# CSM37F58_V6_1.net
KiCad netlist of a schematic drawn in Altium Designer
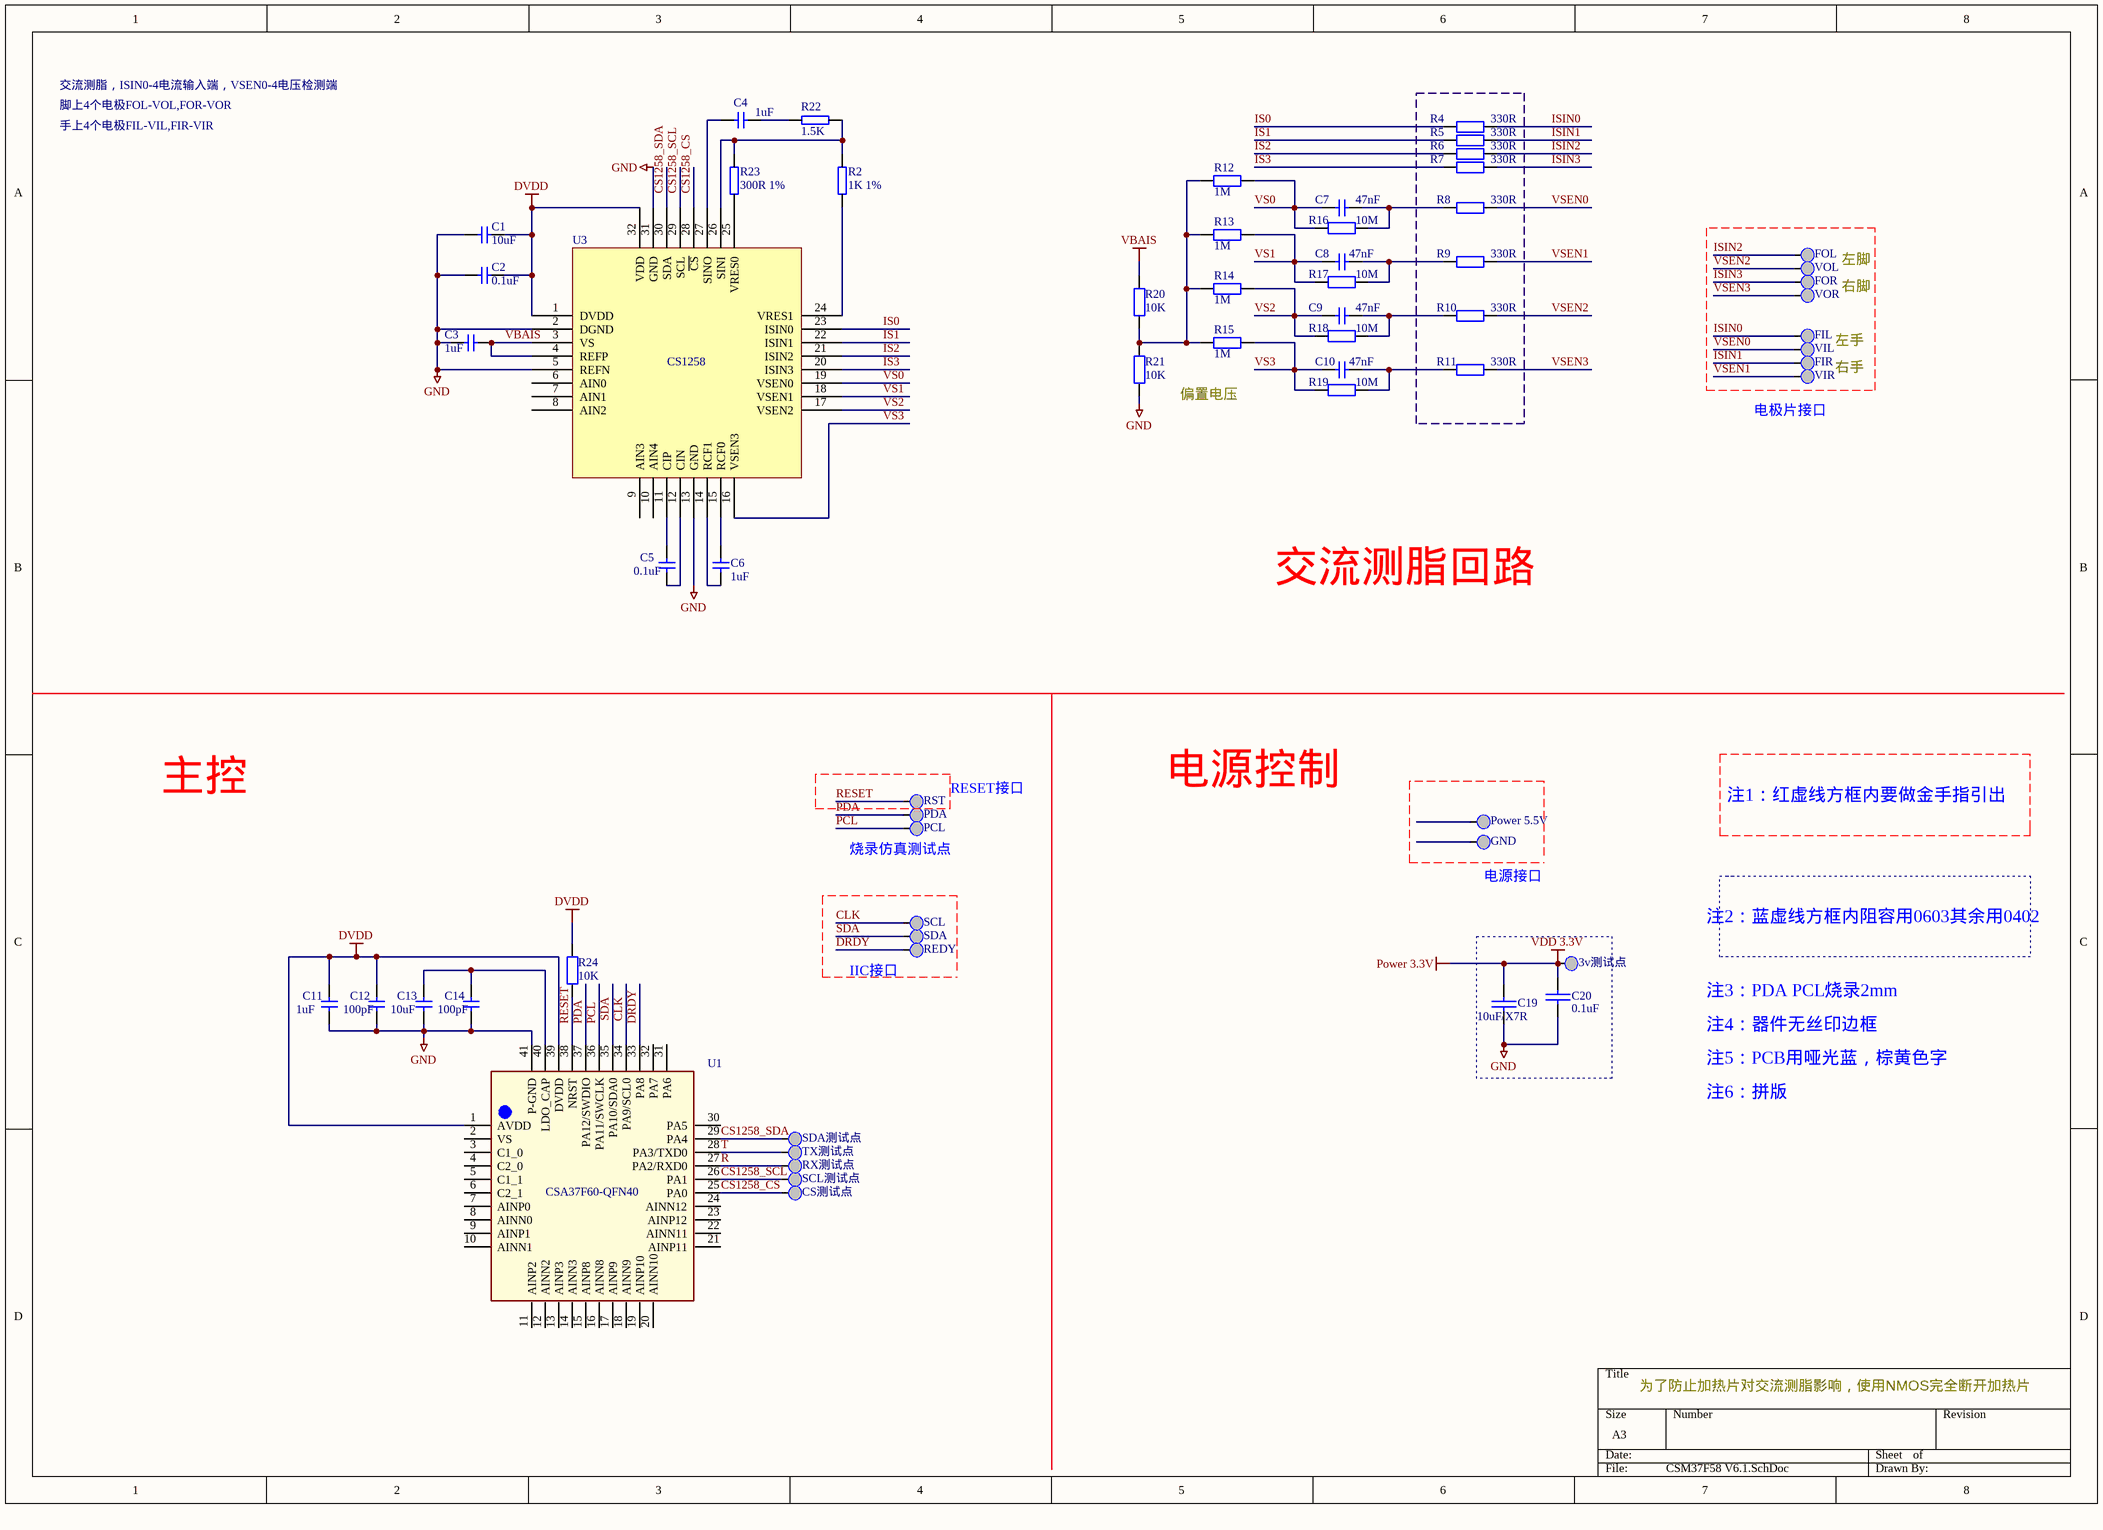
[diagram p0: CSM37F58 V6.1.SchDoc]

(export (version "E")
  (design (tool "Eeschema 10.0.6"))
  (components
    (comp (ref "3v测试点") (value "~") (footprint "TEST-SMD") (libsource (lib "*") (part "TESTPOINT")))
    (comp (ref "C1") (value "10uF") (footprint "C0603E") (libsource (lib "") (part "CAP_1")))
    (comp (ref "C2") (value "0.1uF") (footprint "C0603E") (libsource (lib "") (part "CAP_1")))
    (comp (ref "C3") (value "1uF") (footprint "C0603E") (libsource (lib "") (part "CAP_1")))
    (comp (ref "C4") (value "1uF") (footprint "C0603E") (libsource (lib "") (part "CAP_1")))
    (comp (ref "C5") (value "0.1uF") (footprint "C0603E") (libsource (lib "") (part "CAP_1")))
    (comp (ref "C6") (value "1uF") (footprint "C0603E") (libsource (lib "") (part "CAP_1")))
    (comp (ref "C7") (value "47nF") (footprint "C0603E") (libsource (lib "") (part "CAP_1")))
    (comp (ref "C8") (value "47nF") (footprint "C0603E") (libsource (lib "") (part "CAP_1")))
    (comp (ref "C9") (value "47nF") (footprint "C0603E") (libsource (lib "") (part "CAP_1")))
    (comp (ref "C10") (value "47nF") (footprint "C0603E") (libsource (lib "") (part "CAP_1")))
    (comp (ref "C11") (value "1uF") (footprint "C0603E") (libsource (lib "") (part "CAP_1")))
    (comp (ref "C12") (value "100pF") (footprint "C0603E") (libsource (lib "") (part "CAP_1")))
    (comp (ref "C13") (value "10uF") (footprint "C0603E") (libsource (lib "") (part "CAP_1")))
    (comp (ref "C14") (value "100pF") (footprint "C0603E") (libsource (lib "") (part "CAP_1")))
    (comp (ref "C19")
      (value "10uF/X7R")
      (footprint "C0603")
      (description "Capacitor")
      (libsource (lib "*") (part "CAP"))
    )
    (comp (ref "C20")
      (value "0.1uF")
      (footprint "C0603")
      (description "Capacitor")
      (libsource (lib "*") (part "CAP"))
    )
    (comp (ref "CS测试点") (value "~") (footprint "TEST-SMD") (libsource (lib "*") (part "TESTPOINT")))
    (comp (ref "FIL") (value "TESTPOINT") (footprint "TEST-SMD") (libsource (lib "*") (part "TESTPOINT")))
    (comp (ref "FIR") (value "TESTPOINT") (footprint "TEST-SMD") (libsource (lib "*") (part "TESTPOINT")))
    (comp (ref "FOL") (value "TESTPOINT") (footprint "TEST-SMD") (libsource (lib "*") (part "TESTPOINT")))
    (comp (ref "FOR") (value "TESTPOINT") (footprint "TEST-SMD") (libsource (lib "*") (part "TESTPOINT")))
    (comp (ref "GND") (value "~") (footprint "TEST-SMD") (libsource (lib "*") (part "TESTPOINT")))
    (comp (ref "PCL") (value "~") (footprint "TEST-SMD") (libsource (lib "*") (part "TESTPOINT")))
    (comp (ref "PDA") (value "~") (footprint "TEST-SMD") (libsource (lib "*") (part "TESTPOINT")))
    (comp (ref "Power 5.5V") (value "~") (footprint "TEST-SMD") (libsource (lib "*") (part "TESTPOINT")))
    (comp (ref "R2") (value "1K 1%") (footprint "R0603E") (libsource (lib "*") (part "RES")))
    (comp (ref "R4")
      (value "330R")
      (footprint "R0603E")
      (description "Resistor")
      (fields (field (name "Comment") "Res2") (field (name "PUBLISHER") "Altium Limited"))
      (libsource (lib "Miscellaneous Devices") (part "Res2"))
    )
    (comp (ref "R5")
      (value "330R")
      (footprint "R0603E")
      (description "Resistor")
      (fields (field (name "Comment") "Res2") (field (name "PUBLISHER") "Altium Limited"))
      (libsource (lib "Miscellaneous Devices") (part "Res2"))
    )
    (comp (ref "R6")
      (value "330R")
      (footprint "R0603E")
      (description "Resistor")
      (fields (field (name "Comment") "Res2") (field (name "PUBLISHER") "Altium Limited"))
      (libsource (lib "Miscellaneous Devices") (part "Res2"))
    )
    (comp (ref "R7")
      (value "330R")
      (footprint "R0603E")
      (description "Resistor")
      (fields (field (name "Comment") "Res2") (field (name "PUBLISHER") "Altium Limited"))
      (libsource (lib "Miscellaneous Devices") (part "Res2"))
    )
    (comp (ref "R8")
      (value "330R")
      (footprint "R0603E")
      (description "Resistor")
      (fields (field (name "Comment") "Res2") (field (name "PUBLISHER") "Altium Limited"))
      (libsource (lib "Miscellaneous Devices") (part "Res2"))
    )
    (comp (ref "R9")
      (value "330R")
      (footprint "R0603E")
      (description "Resistor")
      (fields (field (name "Comment") "Res2") (field (name "PUBLISHER") "Altium Limited"))
      (libsource (lib "Miscellaneous Devices") (part "Res2"))
    )
    (comp (ref "R10")
      (value "330R")
      (footprint "R0603E")
      (description "Resistor")
      (fields (field (name "Comment") "Res2") (field (name "PUBLISHER") "Altium Limited"))
      (libsource (lib "Miscellaneous Devices") (part "Res2"))
    )
    (comp (ref "R11")
      (value "330R")
      (footprint "R0603E")
      (description "Resistor")
      (fields (field (name "Comment") "Res2") (field (name "PUBLISHER") "Altium Limited"))
      (libsource (lib "") (part "Res2_1"))
    )
    (comp (ref "R12")
      (value "1M")
      (footprint "R0603E")
      (description "Resistor")
      (fields (field (name "Comment") "Res2") (field (name "PUBLISHER") "Altium Limited"))
      (libsource (lib "") (part "Res2_1"))
    )
    (comp (ref "R13")
      (value "1M")
      (footprint "R0603E")
      (description "Resistor")
      (fields (field (name "Comment") "Res2") (field (name "PUBLISHER") "Altium Limited"))
      (libsource (lib "") (part "Res2_1"))
    )
    (comp (ref "R14")
      (value "1M")
      (footprint "R0603E")
      (description "Resistor")
      (fields (field (name "Comment") "Res2") (field (name "PUBLISHER") "Altium Limited"))
      (libsource (lib "") (part "Res2_1"))
    )
    (comp (ref "R15")
      (value "1M")
      (footprint "R0603E")
      (description "Resistor")
      (fields (field (name "Comment") "Res2") (field (name "PUBLISHER") "Altium Limited"))
      (libsource (lib "") (part "Res2_1"))
    )
    (comp (ref "R16")
      (value "10M")
      (footprint "R0603E")
      (description "Resistor")
      (fields (field (name "Comment") "Res2") (field (name "PUBLISHER") "Altium Limited"))
      (libsource (lib "") (part "Res2_1"))
    )
    (comp (ref "R17")
      (value "10M")
      (footprint "R0603E")
      (description "Resistor")
      (fields (field (name "Comment") "Res2") (field (name "PUBLISHER") "Altium Limited"))
      (libsource (lib "") (part "Res2_1"))
    )
    (comp (ref "R18")
      (value "10M")
      (footprint "R0603E")
      (description "Resistor")
      (fields (field (name "Comment") "Res2") (field (name "PUBLISHER") "Altium Limited"))
      (libsource (lib "") (part "Res2_1"))
    )
    (comp (ref "R19")
      (value "10M")
      (footprint "R0603E")
      (description "Resistor")
      (fields (field (name "Comment") "Res2") (field (name "PUBLISHER") "Altium Limited"))
      (libsource (lib "") (part "Res2_1"))
    )
    (comp (ref "R20")
      (value "10K")
      (footprint "R0603E")
      (description "Resistor")
      (fields (field (name "Comment") "Res2") (field (name "PUBLISHER") "Altium Limited"))
      (libsource (lib "") (part "Res2_3"))
    )
    (comp (ref "R21")
      (value "10K")
      (footprint "R0603E")
      (description "Resistor")
      (fields (field (name "Comment") "Res2") (field (name "PUBLISHER") "Altium Limited"))
      (libsource (lib "") (part "Res2_2"))
    )
    (comp (ref "R22") (value "1.5K") (footprint "R0603E") (libsource (lib "*") (part "RES")))
    (comp (ref "R23") (value "300R 1%") (footprint "R0603E") (libsource (lib "*") (part "RES")))
    (comp (ref "R24")
      (value "10K")
      (footprint "R0603E")
      (description "Resistor")
      (fields (field (name "Comment") "Res2") (field (name "PUBLISHER") "Altium Limited"))
      (libsource (lib "") (part "Res2_2"))
    )
    (comp (ref "REDY") (value "~") (footprint "TEST-SMD") (libsource (lib "*") (part "TESTPOINT")))
    (comp (ref "RST") (value "~") (footprint "TEST-SMD") (libsource (lib "*") (part "TESTPOINT")))
    (comp (ref "RX测试点") (value "~") (footprint "TEST-SMD") (libsource (lib "*") (part "TESTPOINT")))
    (comp (ref "SCL") (value "~") (footprint "TEST-SMD") (libsource (lib "*") (part "TESTPOINT")))
    (comp (ref "SCL测试点") (value "~") (footprint "TEST-SMD") (libsource (lib "*") (part "TESTPOINT")))
    (comp (ref "SDA") (value "~") (footprint "TEST-SMD") (libsource (lib "*") (part "TESTPOINT")))
    (comp (ref "SDA测试点") (value "~") (footprint "TEST-SMD") (libsource (lib "*") (part "TESTPOINT")))
    (comp (ref "TX测试点") (value "~") (footprint "TEST-SMD") (libsource (lib "*") (part "TESTPOINT")))
    (comp (ref "U1")
      (value "CSA37F60-QFN40")
      (footprint "QFN40-04")
      (libsource (lib "Chipsea MCU") (part "CSA37F60-QFN40"))
    )
    (comp (ref "U3") (value "CS1258") (footprint "LQFP32") (libsource (lib "*") (part "CS1258")))
    (comp (ref "VIL") (value "TESTPOINT") (footprint "TEST-SMD") (libsource (lib "*") (part "TESTPOINT")))
    (comp (ref "VIR") (value "TESTPOINT") (footprint "TEST-SMD") (libsource (lib "*") (part "TESTPOINT")))
    (comp (ref "VOL") (value "TESTPOINT") (footprint "TEST-SMD") (libsource (lib "*") (part "TESTPOINT")))
    (comp (ref "VOR") (value "TESTPOINT") (footprint "TEST-SMD") (libsource (lib "*") (part "TESTPOINT")))
  )
  (nets
    (net (code "1") (name "/CLK") (class "Default")
      (node (ref "SCL") (pin "1") (pinfunction "1_1") (pintype "passive"))
      (node (ref "U1") (pin "34") (pinfunction "PA9/SCL0_34") (pintype "passive"))
    )
    (net (code "2") (name "/CS1258_CS") (class "Default")
      (node (ref "CS测试点") (pin "1") (pinfunction "1_1") (pintype "passive"))
      (node (ref "U1") (pin "25") (pinfunction "PA0_25") (pintype "passive"))
      (node (ref "U3") (pin "28") (pinfunction "~{CS}_28") (pintype "passive"))
    )
    (net (code "3") (name "/CS1258_SCL") (class "Default")
      (node (ref "SCL测试点") (pin "1") (pinfunction "1_1") (pintype "passive"))
      (node (ref "U1") (pin "26") (pinfunction "PA1_26") (pintype "passive"))
      (node (ref "U3") (pin "29") (pinfunction "SCL_29") (pintype "passive"))
    )
    (net (code "4") (name "/CS1258_SDA") (class "Default")
      (node (ref "SDA测试点") (pin "1") (pinfunction "1_1") (pintype "passive"))
      (node (ref "U1") (pin "29") (pinfunction "PA4_29") (pintype "passive"))
      (node (ref "U3") (pin "30") (pinfunction "SDA_30") (pintype "passive"))
    )
    (net (code "5") (name "/DRDY") (class "Default")
      (node (ref "REDY") (pin "1") (pinfunction "1_1") (pintype "passive"))
      (node (ref "U1") (pin "33") (pinfunction "PA8_33") (pintype "passive"))
    )
    (net (code "6") (name "/IS0") (class "Default")
      (node (ref "R4") (pin "1") (pinfunction "1_1") (pintype "passive"))
      (node (ref "U3") (pin "23") (pinfunction "ISIN0_23") (pintype "passive"))
    )
    (net (code "7") (name "/IS1") (class "Default")
      (node (ref "R5") (pin "1") (pinfunction "1_1") (pintype "passive"))
      (node (ref "U3") (pin "22") (pinfunction "ISIN1_22") (pintype "passive"))
    )
    (net (code "8") (name "/IS2") (class "Default")
      (node (ref "R6") (pin "1") (pinfunction "1_1") (pintype "passive"))
      (node (ref "U3") (pin "21") (pinfunction "ISIN2_21") (pintype "passive"))
    )
    (net (code "9") (name "/IS3") (class "Default")
      (node (ref "R7") (pin "1") (pinfunction "1_1") (pintype "passive"))
      (node (ref "U3") (pin "20") (pinfunction "ISIN3_20") (pintype "passive"))
    )
    (net (code "10") (name "/ISIN0") (class "Default")
      (node (ref "FIL") (pin "1") (pinfunction "1_1") (pintype "passive"))
      (node (ref "R4") (pin "2") (pinfunction "2_2") (pintype "passive"))
    )
    (net (code "11") (name "/ISIN1") (class "Default")
      (node (ref "FIR") (pin "1") (pinfunction "1_1") (pintype "passive"))
      (node (ref "R5") (pin "2") (pinfunction "2_2") (pintype "passive"))
    )
    (net (code "12") (name "/ISIN2") (class "Default")
      (node (ref "FOL") (pin "1") (pinfunction "1_1") (pintype "passive"))
      (node (ref "R6") (pin "2") (pinfunction "2_2") (pintype "passive"))
    )
    (net (code "13") (name "/ISIN3") (class "Default")
      (node (ref "FOR") (pin "1") (pinfunction "1_1") (pintype "passive"))
      (node (ref "R7") (pin "2") (pinfunction "2_2") (pintype "passive"))
    )
    (net (code "14") (name "/PCL") (class "Default")
      (node (ref "PCL") (pin "1") (pinfunction "1_1") (pintype "passive"))
      (node (ref "U1") (pin "36") (pinfunction "PA11/SWCLK_36") (pintype "passive"))
    )
    (net (code "15") (name "/PDA") (class "Default")
      (node (ref "PDA") (pin "1") (pinfunction "1_1") (pintype "passive"))
      (node (ref "U1") (pin "37") (pinfunction "PA12/SWDIO_37") (pintype "passive"))
    )
    (net (code "16") (name "/R") (class "Default")
      (node (ref "RX测试点") (pin "1") (pinfunction "1_1") (pintype "passive"))
      (node (ref "U1") (pin "27") (pinfunction "PA2/RXD0_27") (pintype "passive"))
    )
    (net (code "17") (name "/RESET") (class "Default")
      (node (ref "R24") (pin "1") (pinfunction "1_1") (pintype "passive"))
      (node (ref "RST") (pin "1") (pinfunction "1_1") (pintype "passive"))
      (node (ref "U1") (pin "38") (pinfunction "NRST_38") (pintype "passive"))
    )
    (net (code "18") (name "/SDA") (class "Default")
      (node (ref "SDA") (pin "1") (pinfunction "1_1") (pintype "passive"))
      (node (ref "U1") (pin "35") (pinfunction "PA10/SDA0_35") (pintype "passive"))
    )
    (net (code "19") (name "/T") (class "Default")
      (node (ref "TX测试点") (pin "1") (pinfunction "1_1") (pintype "passive"))
      (node (ref "U1") (pin "28") (pinfunction "PA3/TXD0_28") (pintype "passive"))
    )
    (net (code "20") (name "/VS0") (class "Default")
      (node (ref "C7") (pin "1") (pintype "passive"))
      (node (ref "R12") (pin "1") (pinfunction "1_1") (pintype "passive"))
      (node (ref "R16") (pin "2") (pinfunction "2_2") (pintype "passive"))
      (node (ref "U3") (pin "19") (pinfunction "VSEN0_19") (pintype "passive"))
    )
    (net (code "21") (name "/VS1") (class "Default")
      (node (ref "C8") (pin "1") (pintype "passive"))
      (node (ref "R13") (pin "1") (pinfunction "1_1") (pintype "passive"))
      (node (ref "R17") (pin "2") (pinfunction "2_2") (pintype "passive"))
      (node (ref "U3") (pin "18") (pinfunction "VSEN1_18") (pintype "passive"))
    )
    (net (code "22") (name "/VS2") (class "Default")
      (node (ref "C9") (pin "1") (pintype "passive"))
      (node (ref "R14") (pin "1") (pinfunction "1_1") (pintype "passive"))
      (node (ref "R18") (pin "2") (pinfunction "2_2") (pintype "passive"))
      (node (ref "U3") (pin "17") (pinfunction "VSEN2_17") (pintype "passive"))
    )
    (net (code "23") (name "/VS3") (class "Default")
      (node (ref "C10") (pin "1") (pintype "passive"))
      (node (ref "R15") (pin "1") (pinfunction "1_1") (pintype "passive"))
      (node (ref "R19") (pin "2") (pinfunction "2_2") (pintype "passive"))
      (node (ref "U3") (pin "16") (pinfunction "VSEN3_16") (pintype "passive"))
    )
    (net (code "24") (name "/VSEN0") (class "Default")
      (node (ref "R8") (pin "2") (pinfunction "2_2") (pintype "passive"))
      (node (ref "VIL") (pin "1") (pinfunction "1_1") (pintype "passive"))
    )
    (net (code "25") (name "/VSEN1") (class "Default")
      (node (ref "R9") (pin "2") (pinfunction "2_2") (pintype "passive"))
      (node (ref "VIR") (pin "1") (pinfunction "1_1") (pintype "passive"))
    )
    (net (code "26") (name "/VSEN2") (class "Default")
      (node (ref "R10") (pin "2") (pinfunction "2_2") (pintype "passive"))
      (node (ref "VOL") (pin "1") (pinfunction "1_1") (pintype "passive"))
    )
    (net (code "27") (name "/VSEN3") (class "Default")
      (node (ref "R11") (pin "1") (pinfunction "1_1") (pintype "passive"))
      (node (ref "VOR") (pin "1") (pinfunction "1_1") (pintype "passive"))
    )
    (net (code "28") (name "DVDD") (class "Default")
      (node (ref "C1") (pin "2") (pintype "passive"))
      (node (ref "C11") (pin "1") (pintype "passive"))
      (node (ref "C12") (pin "1") (pintype "passive"))
      (node (ref "C2") (pin "1") (pintype "passive"))
      (node (ref "R24") (pin "2") (pinfunction "2_2") (pintype "passive"))
      (node (ref "U1") (pin "1") (pinfunction "AVDD_1") (pintype "passive"))
      (node (ref "U1") (pin "39") (pinfunction "DVDD_39") (pintype "passive"))
      (node (ref "U3") (pin "1") (pinfunction "DVDD_1") (pintype "passive"))
      (node (ref "U3") (pin "32") (pinfunction "VDD_32") (pintype "passive"))
    )
    (net (code "29") (name "GND") (class "Default")
      (node (ref "C1") (pin "1") (pintype "passive"))
      (node (ref "C11") (pin "2") (pintype "passive"))
      (node (ref "C12") (pin "2") (pintype "passive"))
      (node (ref "C13") (pin "2") (pintype "passive"))
      (node (ref "C14") (pin "2") (pintype "passive"))
      (node (ref "C19") (pin "2") (pinfunction "2_2") (pintype "passive"))
      (node (ref "C2") (pin "2") (pintype "passive"))
      (node (ref "C20") (pin "2") (pinfunction "2_2") (pintype "passive"))
      (node (ref "C3") (pin "2") (pintype "passive"))
      (node (ref "R21") (pin "1") (pinfunction "1_1") (pintype "passive"))
      (node (ref "U1") (pin "41") (pinfunction "P-GND_41") (pintype "passive"))
      (node (ref "U3") (pin "13") (pinfunction "GND_13") (pintype "passive"))
      (node (ref "U3") (pin "2") (pinfunction "DGND_2") (pintype "passive"))
      (node (ref "U3") (pin "31") (pinfunction "GND_31") (pintype "passive"))
      (node (ref "U3") (pin "5") (pinfunction "REFN_5") (pintype "passive"))
    )
    (net (code "30") (name "Net-(C4-Pad1)") (class "Default")
      (node (ref "C4") (pin "1") (pintype "passive"))
      (node (ref "R22") (pin "2") (pintype "passive"))
    )
    (net (code "31") (name "Net-(C7-Pad2)") (class "Default")
      (node (ref "C7") (pin "2") (pintype "passive"))
      (node (ref "R16") (pin "1") (pinfunction "1_1") (pintype "passive"))
      (node (ref "R8") (pin "1") (pinfunction "1_1") (pintype "passive"))
    )
    (net (code "32") (name "Net-(C8-Pad2)") (class "Default")
      (node (ref "C8") (pin "2") (pintype "passive"))
      (node (ref "R17") (pin "1") (pinfunction "1_1") (pintype "passive"))
      (node (ref "R9") (pin "1") (pinfunction "1_1") (pintype "passive"))
    )
    (net (code "33") (name "Net-(C9-Pad2)") (class "Default")
      (node (ref "C9") (pin "2") (pintype "passive"))
      (node (ref "R10") (pin "1") (pinfunction "1_1") (pintype "passive"))
      (node (ref "R18") (pin "1") (pinfunction "1_1") (pintype "passive"))
    )
    (net (code "34") (name "Net-(C10-Pad2)") (class "Default")
      (node (ref "C10") (pin "2") (pintype "passive"))
      (node (ref "R11") (pin "2") (pinfunction "2_2") (pintype "passive"))
      (node (ref "R19") (pin "1") (pinfunction "1_1") (pintype "passive"))
    )
    (net (code "35") (name "Net-(R12-Pad2)") (class "Default")
      (node (ref "R12") (pin "2") (pinfunction "2_2") (pintype "passive"))
      (node (ref "R13") (pin "2") (pinfunction "2_2") (pintype "passive"))
      (node (ref "R14") (pin "2") (pinfunction "2_2") (pintype "passive"))
      (node (ref "R15") (pin "2") (pinfunction "2_2") (pintype "passive"))
      (node (ref "R20") (pin "2") (pinfunction "2_2") (pintype "passive"))
      (node (ref "R21") (pin "2") (pinfunction "2_2") (pintype "passive"))
    )
    (net (code "36") (name "Net-(U1-LDO_CAP)") (class "Default")
      (node (ref "C13") (pin "1") (pintype "passive"))
      (node (ref "C14") (pin "1") (pintype "passive"))
      (node (ref "U1") (pin "40") (pinfunction "LDO_CAP_40") (pintype "passive"))
    )
    (net (code "37") (name "Net-(U3-CIN)") (class "Default")
      (node (ref "C5") (pin "2") (pintype "passive"))
      (node (ref "U3") (pin "12") (pinfunction "CIN_12") (pintype "passive"))
    )
    (net (code "38") (name "Net-(U3-CIP)") (class "Default")
      (node (ref "C5") (pin "1") (pintype "passive"))
      (node (ref "U3") (pin "11") (pinfunction "CIP_11") (pintype "passive"))
    )
    (net (code "39") (name "Net-(U3-RCF0)") (class "Default")
      (node (ref "C6") (pin "2") (pintype "passive"))
      (node (ref "U3") (pin "15") (pinfunction "RCF0_15") (pintype "passive"))
    )
    (net (code "40") (name "Net-(U3-RCF1)") (class "Default")
      (node (ref "C6") (pin "1") (pintype "passive"))
      (node (ref "U3") (pin "14") (pinfunction "RCF1_14") (pintype "passive"))
    )
    (net (code "41") (name "Net-(U3-SINI)") (class "Default")
      (node (ref "R2") (pin "2") (pintype "passive"))
      (node (ref "R22") (pin "1") (pintype "passive"))
      (node (ref "R23") (pin "1") (pintype "passive"))
      (node (ref "U3") (pin "26") (pinfunction "SINI_26") (pintype "passive"))
    )
    (net (code "42") (name "Net-(U3-SINO)") (class "Default")
      (node (ref "C4") (pin "2") (pintype "passive"))
      (node (ref "U3") (pin "27") (pinfunction "SINO_27") (pintype "passive"))
    )
    (net (code "43") (name "Net-(U3-VRES0)") (class "Default")
      (node (ref "R23") (pin "2") (pintype "passive"))
      (node (ref "U3") (pin "25") (pinfunction "VRES0_25") (pintype "passive"))
    )
    (net (code "44") (name "Net-(U3-VRES1)") (class "Default")
      (node (ref "R2") (pin "1") (pintype "passive"))
      (node (ref "U3") (pin "24") (pinfunction "VRES1_24") (pintype "passive"))
    )
    (net (code "45") (name "Power 3.3V") (class "Default")
      (node (ref "3v测试点") (pin "1") (pinfunction "1_1") (pintype "passive"))
      (node (ref "C19") (pin "1") (pinfunction "1_1") (pintype "passive"))
      (node (ref "C20") (pin "1") (pinfunction "1_1") (pintype "passive"))
    )
    (net (code "46") (name "VBAIS") (class "Default")
      (node (ref "C3") (pin "1") (pintype "passive"))
      (node (ref "R20") (pin "1") (pinfunction "1_1") (pintype "passive"))
      (node (ref "U3") (pin "3") (pinfunction "VS_3") (pintype "passive"))
      (node (ref "U3") (pin "4") (pinfunction "REFP_4") (pintype "passive"))
    )
    (net (code "47") (name "unconnected-(GND-Pad1)") (class "Default")
      (node (ref "GND") (pin "1") (pinfunction "1_1") (pintype "passive"))
    )
    (net (code "48") (name "unconnected-(Power 5.5V-Pad1)") (class "Default")
      (node (ref "Power 5.5V") (pin "1") (pinfunction "1_1") (pintype "passive"))
    )
    (net (code "49") (name "unconnected-(U1-AINN0-Pad8)") (class "Default")
      (node (ref "U1") (pin "8") (pinfunction "AINN0_8") (pintype "passive"))
    )
    (net (code "50") (name "unconnected-(U1-AINN1-Pad10)") (class "Default")
      (node (ref "U1") (pin "10") (pinfunction "AINN1_10") (pintype "passive"))
    )
    (net (code "51") (name "unconnected-(U1-AINN2-Pad12)") (class "Default")
      (node (ref "U1") (pin "12") (pinfunction "AINN2_12") (pintype "passive"))
    )
    (net (code "52") (name "unconnected-(U1-AINN3-Pad14)") (class "Default")
      (node (ref "U1") (pin "14") (pinfunction "AINN3_14") (pintype "passive"))
    )
    (net (code "53") (name "unconnected-(U1-AINN8-Pad16)") (class "Default")
      (node (ref "U1") (pin "16") (pinfunction "AINN8_16") (pintype "passive"))
    )
    (net (code "54") (name "unconnected-(U1-AINN9-Pad18)") (class "Default")
      (node (ref "U1") (pin "18") (pinfunction "AINN9_18") (pintype "passive"))
    )
    (net (code "55") (name "unconnected-(U1-AINN10-Pad20)") (class "Default")
      (node (ref "U1") (pin "20") (pinfunction "AINN10_20") (pintype "passive"))
    )
    (net (code "56") (name "unconnected-(U1-AINN11-Pad22)") (class "Default")
      (node (ref "U1") (pin "22") (pinfunction "AINN11_22") (pintype "passive"))
    )
    (net (code "57") (name "unconnected-(U1-AINN12-Pad24)") (class "Default")
      (node (ref "U1") (pin "24") (pinfunction "AINN12_24") (pintype "passive"))
    )
    (net (code "58") (name "unconnected-(U1-AINP0-Pad7)") (class "Default")
      (node (ref "U1") (pin "7") (pinfunction "AINP0_7") (pintype "passive"))
    )
    (net (code "59") (name "unconnected-(U1-AINP1-Pad9)") (class "Default")
      (node (ref "U1") (pin "9") (pinfunction "AINP1_9") (pintype "passive"))
    )
    (net (code "60") (name "unconnected-(U1-AINP2-Pad11)") (class "Default")
      (node (ref "U1") (pin "11") (pinfunction "AINP2_11") (pintype "passive"))
    )
    (net (code "61") (name "unconnected-(U1-AINP3-Pad13)") (class "Default")
      (node (ref "U1") (pin "13") (pinfunction "AINP3_13") (pintype "passive"))
    )
    (net (code "62") (name "unconnected-(U1-AINP8-Pad15)") (class "Default")
      (node (ref "U1") (pin "15") (pinfunction "AINP8_15") (pintype "passive"))
    )
    (net (code "63") (name "unconnected-(U1-AINP9-Pad17)") (class "Default")
      (node (ref "U1") (pin "17") (pinfunction "AINP9_17") (pintype "passive"))
    )
    (net (code "64") (name "unconnected-(U1-AINP10-Pad19)") (class "Default")
      (node (ref "U1") (pin "19") (pinfunction "AINP10_19") (pintype "passive"))
    )
    (net (code "65") (name "unconnected-(U1-AINP11-Pad21)") (class "Default")
      (node (ref "U1") (pin "21") (pinfunction "AINP11_21") (pintype "passive"))
    )
    (net (code "66") (name "unconnected-(U1-AINP12-Pad23)") (class "Default")
      (node (ref "U1") (pin "23") (pinfunction "AINP12_23") (pintype "passive"))
    )
    (net (code "67") (name "unconnected-(U1-C1_0-Pad3)") (class "Default")
      (node (ref "U1") (pin "3") (pinfunction "C1_0_3") (pintype "passive"))
    )
    (net (code "68") (name "unconnected-(U1-C1_1-Pad5)") (class "Default")
      (node (ref "U1") (pin "5") (pinfunction "C1_1_5") (pintype "passive"))
    )
    (net (code "69") (name "unconnected-(U1-C2_0-Pad4)") (class "Default")
      (node (ref "U1") (pin "4") (pinfunction "C2_0_4") (pintype "passive"))
    )
    (net (code "70") (name "unconnected-(U1-C2_1-Pad6)") (class "Default")
      (node (ref "U1") (pin "6") (pinfunction "C2_1_6") (pintype "passive"))
    )
    (net (code "71") (name "unconnected-(U1-PA5-Pad30)") (class "Default")
      (node (ref "U1") (pin "30") (pinfunction "PA5_30") (pintype "passive"))
    )
    (net (code "72") (name "unconnected-(U1-PA6-Pad31)") (class "Default")
      (node (ref "U1") (pin "31") (pinfunction "PA6_31") (pintype "passive"))
    )
    (net (code "73") (name "unconnected-(U1-PA7-Pad32)") (class "Default")
      (node (ref "U1") (pin "32") (pinfunction "PA7_32") (pintype "passive"))
    )
    (net (code "74") (name "unconnected-(U1-VS-Pad2)") (class "Default")
      (node (ref "U1") (pin "2") (pinfunction "VS_2") (pintype "passive"))
    )
    (net (code "75") (name "unconnected-(U3-AIN0-Pad6)") (class "Default")
      (node (ref "U3") (pin "6") (pinfunction "AIN0_6") (pintype "passive"))
    )
    (net (code "76") (name "unconnected-(U3-AIN1-Pad7)") (class "Default")
      (node (ref "U3") (pin "7") (pinfunction "AIN1_7") (pintype "passive"))
    )
    (net (code "77") (name "unconnected-(U3-AIN2-Pad8)") (class "Default")
      (node (ref "U3") (pin "8") (pinfunction "AIN2_8") (pintype "passive"))
    )
    (net (code "78") (name "unconnected-(U3-AIN3-Pad9)") (class "Default")
      (node (ref "U3") (pin "9") (pinfunction "AIN3_9") (pintype "passive"))
    )
    (net (code "79") (name "unconnected-(U3-AIN4-Pad10)") (class "Default")
      (node (ref "U3") (pin "10") (pinfunction "AIN4_10") (pintype "passive"))
    )
  )
)
